# USB-C_Adapter.net
KiCad netlist of a schematic drawn in Altium Designer
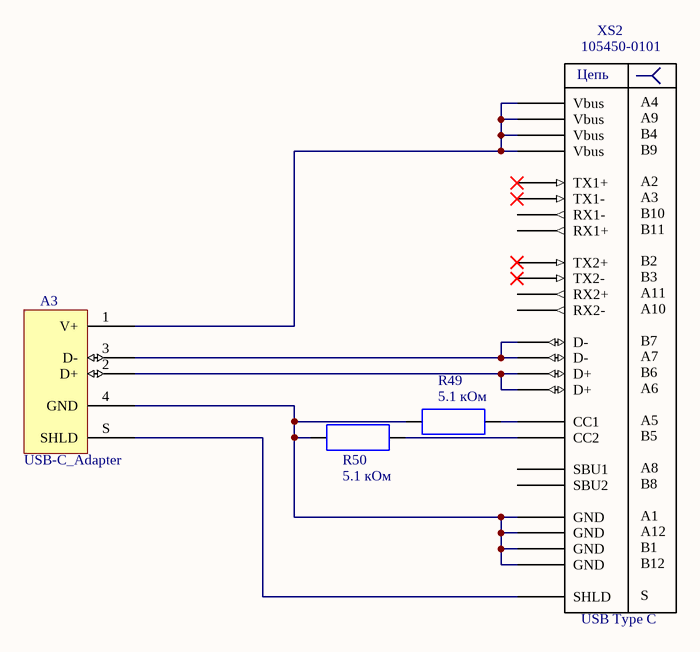
[diagram p0: USB-C_Adapter.SchDoc]

(export (version "E")
  (design (tool "Eeschema 10.0.6"))
  (components
    (comp (ref "A3")
      (value "USB-C_Adapter")
      (footprint "Usb-C_Adapter")
      (libsource (lib "CustomSymbols") (part "USB-C_Adapter"))
    )
    (comp (ref "R49")
      (value "5.1 кОм")
      (footprint "RES_0603-1608")
      (description "Резистор постоянный")
      (fields (field (name "POWER") "0.125 W") (field (name "TOLERANCE") "5%"))
      (libsource (lib "GOST_Generic") (part "Res"))
    )
    (comp (ref "R50")
      (value "5.1 кОм")
      (footprint "RES_0603-1608")
      (description "Резистор постоянный")
      (fields (field (name "POWER") "0.125 W") (field (name "TOLERANCE") "5%"))
      (libsource (lib "GOST_Generic") (part "Res"))
    )
    (comp (ref "XS2")
      (value "USB Type C")
      (footprint "105450-0101")
      (fields (field (name "TYPE") "105450-0101"))
      (libsource (lib "Стандартные соединители") (part "USB-C_Generic"))
    )
  )
  (nets
    (net (code "1") (name "Net-(A3-D+)") (class "Default")
      (node (ref "A3") (pin "2") (pinfunction "D+_2") (pintype "bidirectional"))
      (node (ref "XS2") (pin "A6") (pinfunction "D+_A6") (pintype "bidirectional"))
      (node (ref "XS2") (pin "B6") (pinfunction "D+_B6") (pintype "bidirectional"))
    )
    (net (code "2") (name "Net-(A3-D-)") (class "Default")
      (node (ref "A3") (pin "3") (pinfunction "D-_3") (pintype "bidirectional"))
      (node (ref "XS2") (pin "A7") (pinfunction "D-_A7") (pintype "bidirectional"))
      (node (ref "XS2") (pin "B7") (pinfunction "D-_B7") (pintype "bidirectional"))
    )
    (net (code "3") (name "Net-(A3-GND)") (class "Default")
      (node (ref "A3") (pin "4") (pinfunction "GND_4") (pintype "power_in"))
      (node (ref "R49") (pin "2") (pintype "passive"))
      (node (ref "R50") (pin "2") (pintype "passive"))
      (node (ref "XS2") (pin "A1") (pinfunction "GND_A1") (pintype "power_in"))
      (node (ref "XS2") (pin "A12") (pinfunction "GND_A12") (pintype "power_in"))
      (node (ref "XS2") (pin "B1") (pinfunction "GND_B1") (pintype "power_in"))
      (node (ref "XS2") (pin "B12") (pinfunction "GND_B12") (pintype "power_in"))
    )
    (net (code "4") (name "Net-(A3-SHLD)") (class "Default")
      (node (ref "A3") (pin "S") (pinfunction "SHLD_S") (pintype "passive"))
      (node (ref "XS2") (pin "S") (pinfunction "SHLD_S") (pintype "power_in"))
    )
    (net (code "5") (name "Net-(A3-V+)") (class "Default")
      (node (ref "A3") (pin "1") (pinfunction "V+_1") (pintype "power_in"))
      (node (ref "XS2") (pin "A4") (pinfunction "Vbus_A4") (pintype "power_in"))
      (node (ref "XS2") (pin "A9") (pinfunction "Vbus_A9") (pintype "power_in"))
      (node (ref "XS2") (pin "B4") (pinfunction "Vbus_B4") (pintype "power_in"))
      (node (ref "XS2") (pin "B9") (pinfunction "Vbus_B9") (pintype "power_in"))
    )
    (net (code "6") (name "Net-(XS2-CC1)") (class "Default")
      (node (ref "R49") (pin "1") (pintype "passive"))
      (node (ref "XS2") (pin "A5") (pinfunction "CC1_A5") (pintype "passive"))
    )
    (net (code "7") (name "Net-(XS2-CC2)") (class "Default")
      (node (ref "R50") (pin "1") (pintype "passive"))
      (node (ref "XS2") (pin "B5") (pinfunction "CC2_B5") (pintype "passive"))
    )
    (net (code "8") (name "unconnected-(XS2-RX1+-PadB11)") (class "Default")
      (node (ref "XS2") (pin "B11") (pinfunction "RX1+_B11") (pintype "output"))
    )
    (net (code "9") (name "unconnected-(XS2-RX1--PadB10)") (class "Default")
      (node (ref "XS2") (pin "B10") (pinfunction "RX1-_B10") (pintype "output"))
    )
    (net (code "10") (name "unconnected-(XS2-RX2+-PadA11)") (class "Default")
      (node (ref "XS2") (pin "A11") (pinfunction "RX2+_A11") (pintype "output"))
    )
    (net (code "11") (name "unconnected-(XS2-RX2--PadA10)") (class "Default")
      (node (ref "XS2") (pin "A10") (pinfunction "RX2-_A10") (pintype "output"))
    )
    (net (code "12") (name "unconnected-(XS2-SBU1-PadA8)") (class "Default")
      (node (ref "XS2") (pin "A8") (pinfunction "SBU1_A8") (pintype "passive"))
    )
    (net (code "13") (name "unconnected-(XS2-SBU2-PadB8)") (class "Default")
      (node (ref "XS2") (pin "B8") (pinfunction "SBU2_B8") (pintype "passive"))
    )
    (net (code "14") (name "unconnected-(XS2-TX1+-PadA2)") (class "Default")
      (node (ref "XS2") (pin "A2") (pinfunction "TX1+_A2") (pintype "input+no_connect"))
    )
    (net (code "15") (name "unconnected-(XS2-TX1--PadA3)") (class "Default")
      (node (ref "XS2") (pin "A3") (pinfunction "TX1-_A3") (pintype "input+no_connect"))
    )
    (net (code "16") (name "unconnected-(XS2-TX2+-PadB2)") (class "Default")
      (node (ref "XS2") (pin "B2") (pinfunction "TX2+_B2") (pintype "input+no_connect"))
    )
    (net (code "17") (name "unconnected-(XS2-TX2--PadB3)") (class "Default")
      (node (ref "XS2") (pin "B3") (pinfunction "TX2-_B3") (pintype "input+no_connect"))
    )
  )
)
